# PSX_Radio.net
KiCad netlist of a schematic drawn in EAGLE
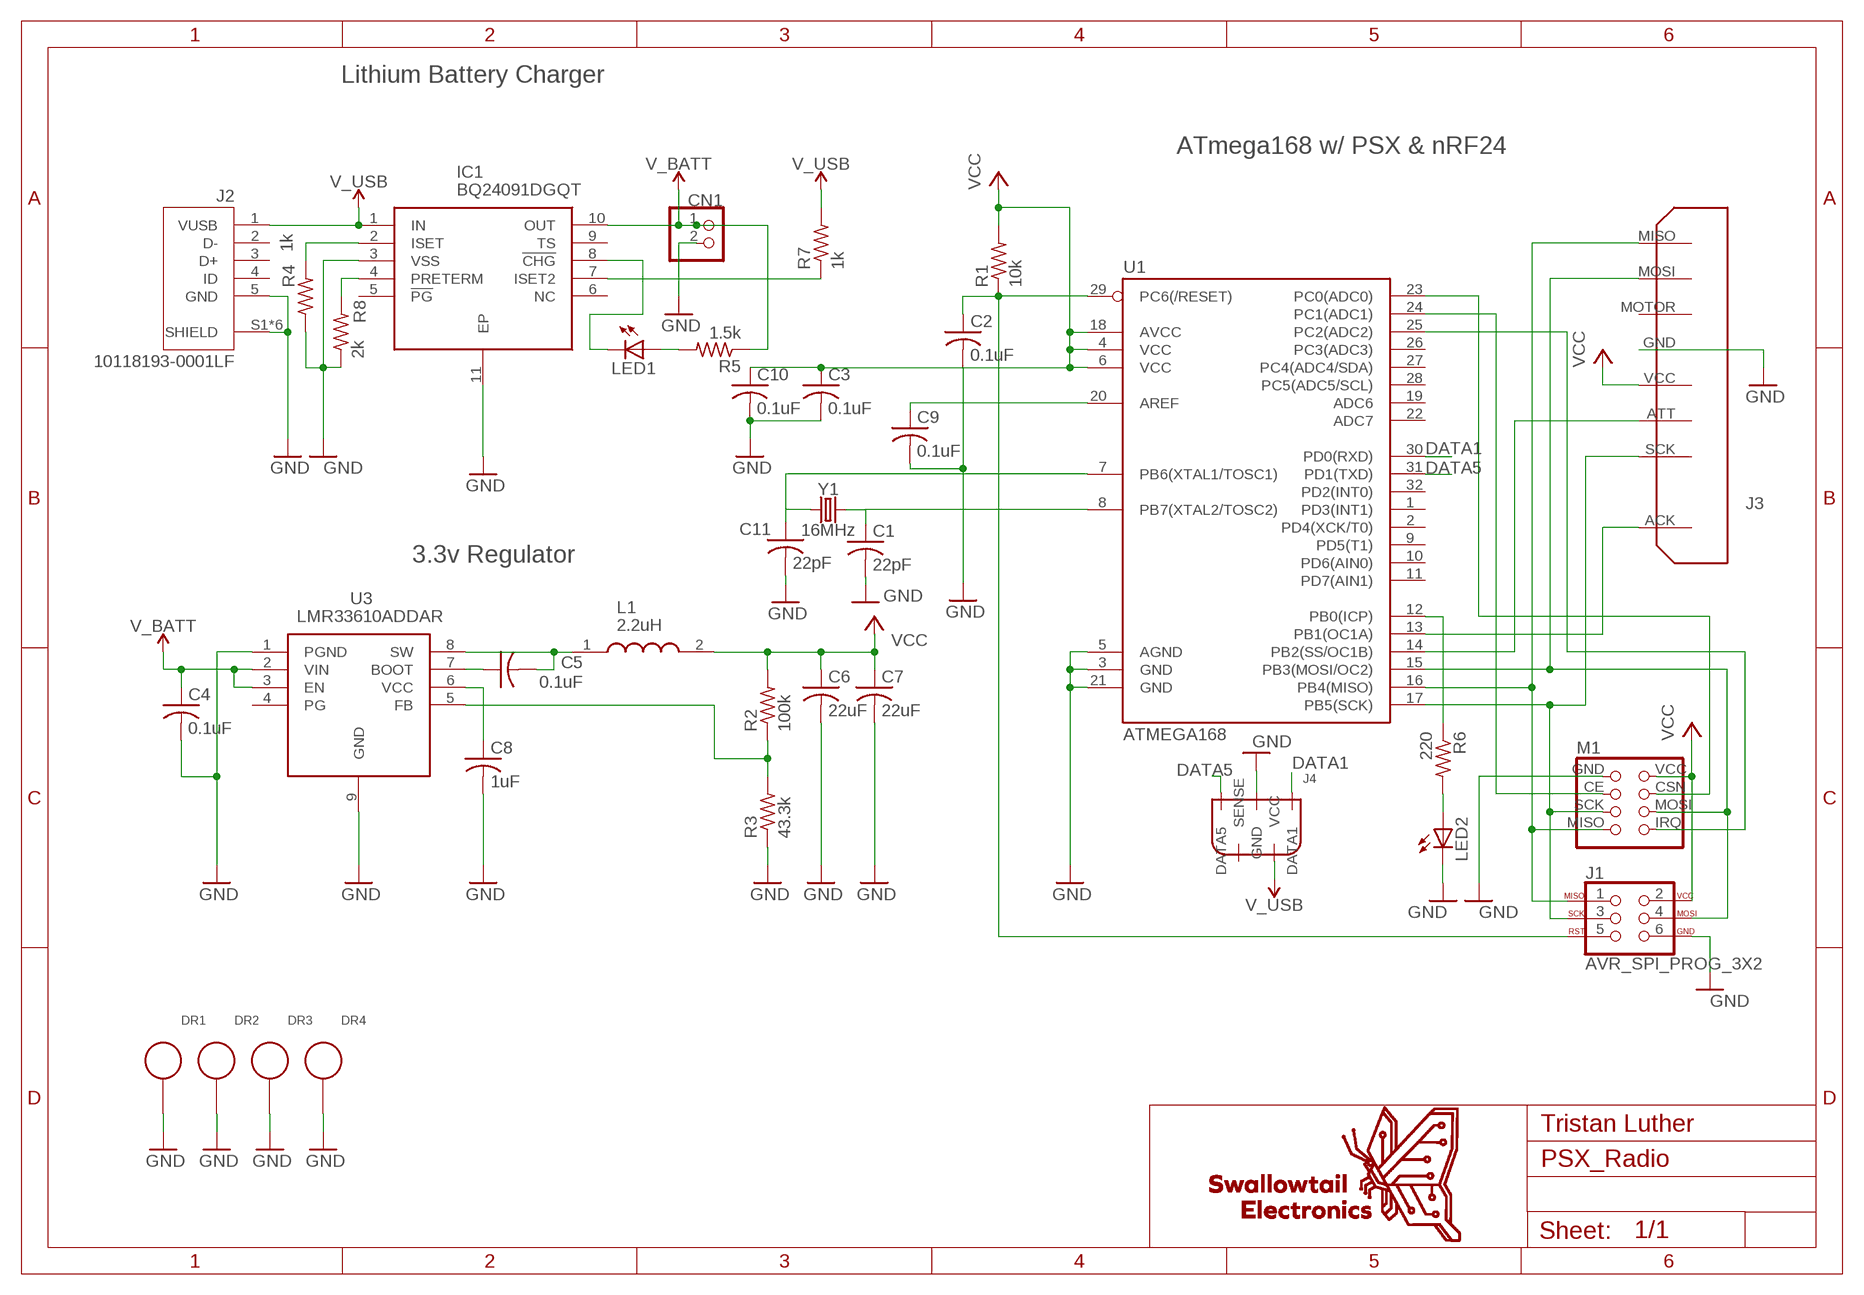
[diagram p0: schematic, sheet 1]

(export (version "E")
  (design (tool "Eeschema 10.0.6"))
  (components
    (comp (ref "C1")
      (value "22pF")
      (footprint "eagle-import:C0805")
      (libsource (lib "eagle-import") (part "C-USC0805"))
    )
    (comp (ref "C2")
      (value "0.1uF")
      (footprint "eagle-import:C0805")
      (libsource (lib "eagle-import") (part "C-USC0805"))
    )
    (comp (ref "C3")
      (value "0.1uF")
      (footprint "eagle-import:C0805")
      (libsource (lib "eagle-import") (part "C-USC0805"))
    )
    (comp (ref "C4")
      (value "0.1uF")
      (footprint "eagle-import:C0805")
      (libsource (lib "eagle-import") (part "C-USC0805"))
    )
    (comp (ref "C5")
      (value "0.1uF")
      (footprint "eagle-import:C0805")
      (libsource (lib "eagle-import") (part "C-USC0805"))
    )
    (comp (ref "C6")
      (value "22uF")
      (footprint "eagle-import:C0805")
      (libsource (lib "eagle-import") (part "C-USC0805"))
    )
    (comp (ref "C7")
      (value "22uF")
      (footprint "eagle-import:C0805")
      (libsource (lib "eagle-import") (part "C-USC0805"))
    )
    (comp (ref "C8")
      (value "1uF")
      (footprint "eagle-import:C0805")
      (libsource (lib "eagle-import") (part "C-USC0805"))
    )
    (comp (ref "C9")
      (value "0.1uF")
      (footprint "eagle-import:C0805")
      (libsource (lib "eagle-import") (part "C-USC0805"))
    )
    (comp (ref "C10")
      (value "0.1uF")
      (footprint "eagle-import:C0805")
      (libsource (lib "eagle-import") (part "C-USC0805"))
    )
    (comp (ref "C11")
      (value "22pF")
      (footprint "eagle-import:C0805")
      (libsource (lib "eagle-import") (part "C-USC0805"))
    )
    (comp (ref "CN1")
      (value "JST_2PIN-SMT-RA")
      (footprint "eagle-import:JST-PH-2-SMT-RA")
      (libsource (lib "eagle-import") (part "JST_2PIN-SMT-RA"))
    )
    (comp (ref "DR1")
      (value "3MM_DRILL_GND")
      (footprint "eagle-import:3MM_DRILL_GND")
      (libsource (lib "eagle-import") (part "3MM_DRILL_GND"))
    )
    (comp (ref "DR2")
      (value "3MM_DRILL_GND")
      (footprint "eagle-import:3MM_DRILL_GND")
      (libsource (lib "eagle-import") (part "3MM_DRILL_GND"))
    )
    (comp (ref "DR3")
      (value "3MM_DRILL_GND")
      (footprint "eagle-import:3MM_DRILL_GND")
      (libsource (lib "eagle-import") (part "3MM_DRILL_GND"))
    )
    (comp (ref "DR4")
      (value "3MM_DRILL_GND")
      (footprint "eagle-import:3MM_DRILL_GND")
      (libsource (lib "eagle-import") (part "3MM_DRILL_GND"))
    )
    (comp (ref "IC1")
      (value "BQ24091DGQT")
      (footprint "eagle-import:SOP50P490X110-11N")
      (fields (field (name "MOUSER_PART_NUMBER") "595-BQ24091DGQT"))
      (libsource (lib "eagle-import") (part "BQ24091DGQT"))
    )
    (comp (ref "J1")
      (value "AVR_SPI_PROG_3X2")
      (footprint "eagle-import:2X3-NS")
      (libsource (lib "eagle-import") (part "AVR_SPI_PROG_3X2"))
    )
    (comp (ref "J2")
      (value "10118193-0001LF")
      (footprint "eagle-import:FCI_10118193-0001LF")
      (fields (field (name "MF") "Amphenol ICC"))
      (libsource (lib "eagle-import") (part "10118193-0001LF"))
    )
    (comp (ref "J3")
      (value "PSX_CONTROLLER")
      (footprint "eagle-import:PSX_VERTICAL")
      (libsource (lib "eagle-import") (part "PSX_CONTROLLER"))
    )
    (comp (ref "J4")
      (value "DREAMCAST_CONTROLLER")
      (footprint "eagle-import:1X06")
      (libsource (lib "eagle-import") (part "DREAMCAST_CONTROLLER"))
    )
    (comp (ref "L1")
      (value "2.2uH")
      (footprint "eagle-import:INDPM5752X150N")
      (fields
        (field (name "ARROW_PART_NUMBER") "SRP5015TA-2R2M")
        (field (name "MOUSER_PART_NUMBER") "652-SRP5015TA-2R2M")
      )
      (libsource (lib "eagle-import") (part "SRP5015TA-2R2M"))
    )
    (comp (ref "LED1")
      (value "LED5MM")
      (footprint "eagle-import:LED5MM")
      (libsource (lib "eagle-import") (part "LED5MM"))
    )
    (comp (ref "LED2")
      (value "LED5MM")
      (footprint "eagle-import:LED5MM")
      (libsource (lib "eagle-import") (part "LED5MM"))
    )
    (comp (ref "M1")
      (value "NRF24L01_MODULE")
      (footprint "eagle-import:2X04")
      (libsource (lib "eagle-import") (part "NRF24L01_MODULE"))
    )
    (comp (ref "R1")
      (value "10k")
      (footprint "eagle-import:R0805")
      (libsource (lib "eagle-import") (part "R-US_R0805"))
    )
    (comp (ref "R2")
      (value "100k")
      (footprint "eagle-import:R0805")
      (libsource (lib "eagle-import") (part "R-US_R0805"))
    )
    (comp (ref "R3")
      (value "43.3k")
      (footprint "eagle-import:R0805")
      (libsource (lib "eagle-import") (part "R-US_R0805"))
    )
    (comp (ref "R4")
      (value "1k")
      (footprint "eagle-import:R0805")
      (libsource (lib "eagle-import") (part "R-US_R0805"))
    )
    (comp (ref "R5")
      (value "1.5k")
      (footprint "eagle-import:R0805")
      (libsource (lib "eagle-import") (part "R-US_R0805"))
    )
    (comp (ref "R6")
      (value "220")
      (footprint "eagle-import:R0805")
      (libsource (lib "eagle-import") (part "R-US_R0805"))
    )
    (comp (ref "R7")
      (value "1k")
      (footprint "eagle-import:R0805")
      (libsource (lib "eagle-import") (part "R-US_R0805"))
    )
    (comp (ref "R8")
      (value "2k")
      (footprint "eagle-import:R0805")
      (libsource (lib "eagle-import") (part "R-US_R0805"))
    )
    (comp (ref "U1")
      (value "ATMEGA168")
      (footprint "eagle-import:TQFP32-08")
      (libsource (lib "eagle-import") (part "ATMEGA168"))
    )
    (comp (ref "U3")
      (value "LMR33610ADDAR")
      (footprint "eagle-import:SOIC127P600X170-9N")
      (fields
        (field (name "ARROW_PART_NUMBER") "LMR33630ADDAR")
        (field (name "MOUSER_PART_NUMBER") "595-LMR33630ADDAR")
      )
      (libsource (lib "eagle-import") (part "LMR33610ADDAR"))
    )
    (comp (ref "Y1")
      (value "16MHz")
      (footprint "eagle-import:CRYSTAL-SMD-5X3.2-4PAD")
      (libsource (lib "eagle-import") (part "CRYSTAL-16MHZSMD-5X3.2"))
    )
  )
  (nets
    (net (code "1") (name "/DATA1") (class "Default")
      (node (ref "J4") (pin "2") (pinfunction "DATA1_2") (pintype "bidirectional"))
      (node (ref "U1") (pin "30") (pinfunction "PD0(RXD)_30") (pintype "bidirectional"))
    )
    (net (code "2") (name "/DATA5") (class "Default")
      (node (ref "J4") (pin "4") (pinfunction "DATA5_4") (pintype "bidirectional"))
      (node (ref "U1") (pin "31") (pinfunction "PD1(TXD)_31") (pintype "bidirectional"))
    )
    (net (code "3") (name "GND") (class "Default")
      (node (ref "C1") (pin "2") (pinfunction "2_2") (pintype "passive"))
      (node (ref "C10") (pin "2") (pinfunction "2_2") (pintype "passive"))
      (node (ref "C11") (pin "2") (pinfunction "2_2") (pintype "passive"))
      (node (ref "C2") (pin "2") (pinfunction "2_2") (pintype "passive"))
      (node (ref "C3") (pin "2") (pinfunction "2_2") (pintype "passive"))
      (node (ref "C4") (pin "2") (pinfunction "2_2") (pintype "passive"))
      (node (ref "C6") (pin "2") (pinfunction "2_2") (pintype "passive"))
      (node (ref "C7") (pin "2") (pinfunction "2_2") (pintype "passive"))
      (node (ref "C8") (pin "2") (pinfunction "2_2") (pintype "passive"))
      (node (ref "C9") (pin "2") (pinfunction "2_2") (pintype "passive"))
      (node (ref "CN1") (pin "2") (pinfunction "1_2") (pintype "passive"))
      (node (ref "DR1") (pin "DR") (pinfunction "D$1_DR") (pintype "bidirectional"))
      (node (ref "DR2") (pin "DR") (pinfunction "D$1_DR") (pintype "bidirectional"))
      (node (ref "DR3") (pin "DR") (pinfunction "D$1_DR") (pintype "bidirectional"))
      (node (ref "DR4") (pin "DR") (pinfunction "D$1_DR") (pintype "bidirectional"))
      (node (ref "IC1") (pin "11") (pinfunction "EP_11") (pintype "bidirectional"))
      (node (ref "IC1") (pin "3") (pinfunction "VSS_3") (pintype "bidirectional"))
      (node (ref "J1") (pin "6") (pinfunction "6_6") (pintype "passive"))
      (node (ref "J2") (pin "5") (pinfunction "GND_5") (pintype "passive"))
      (node (ref "J2") (pin "S1") (pinfunction "SHIELD_S1") (pintype "passive"))
      (node (ref "J2") (pin "S2") (pinfunction "SHIELD_S2") (pintype "passive"))
      (node (ref "J2") (pin "S3") (pinfunction "SHIELD_S3") (pintype "passive"))
      (node (ref "J2") (pin "S4") (pinfunction "SHIELD_S4") (pintype "passive"))
      (node (ref "J2") (pin "S5") (pinfunction "SHIELD_S5") (pintype "passive"))
      (node (ref "J2") (pin "S6") (pinfunction "SHIELD_S6") (pintype "passive"))
      (node (ref "J3") (pin "GND") (pinfunction "GND_GND") (pintype "bidirectional"))
      (node (ref "J4") (pin "5") (pinfunction "GND_5") (pintype "power_in"))
      (node (ref "LED2") (pin "K") (pinfunction "C_K") (pintype "passive"))
      (node (ref "M1") (pin "GND") (pinfunction "GND_GND") (pintype "passive"))
      (node (ref "R3") (pin "1") (pinfunction "1_1") (pintype "passive"))
      (node (ref "R4") (pin "1") (pinfunction "1_1") (pintype "passive"))
      (node (ref "R8") (pin "1") (pinfunction "1_1") (pintype "passive"))
      (node (ref "U1") (pin "21") (pinfunction "GND_21") (pintype "bidirectional"))
      (node (ref "U1") (pin "3") (pinfunction "GND_3") (pintype "bidirectional"))
      (node (ref "U1") (pin "5") (pinfunction "AGND_5") (pintype "bidirectional"))
      (node (ref "U3") (pin "1") (pinfunction "PGND_1") (pintype "bidirectional"))
      (node (ref "U3") (pin "9") (pinfunction "GND_9") (pintype "bidirectional"))
    )
    (net (code "4") (name "Net-(IC1-ISET)") (class "Default")
      (node (ref "IC1") (pin "2") (pinfunction "ISET_2") (pintype "bidirectional"))
      (node (ref "R4") (pin "2") (pinfunction "2_2") (pintype "passive"))
    )
    (net (code "5") (name "Net-(IC1-ISET2)") (class "Default")
      (node (ref "IC1") (pin "7") (pinfunction "ISET2_7") (pintype "bidirectional"))
      (node (ref "R7") (pin "1") (pinfunction "1_1") (pintype "passive"))
    )
    (net (code "6") (name "Net-(IC1-PRETERM)") (class "Default")
      (node (ref "IC1") (pin "4") (pinfunction "PRETERM_4") (pintype "bidirectional"))
      (node (ref "R8") (pin "2") (pinfunction "2_2") (pintype "passive"))
    )
    (net (code "7") (name "Net-(IC1-~{CHG})") (class "Default")
      (node (ref "IC1") (pin "8") (pinfunction "~{CHG}_8") (pintype "bidirectional"))
      (node (ref "LED1") (pin "K") (pinfunction "C_K") (pintype "passive"))
    )
    (net (code "8") (name "Net-(LED1-PadA)") (class "Default")
      (node (ref "LED1") (pin "A") (pinfunction "A_A") (pintype "passive"))
      (node (ref "R5") (pin "2") (pinfunction "2_2") (pintype "passive"))
    )
    (net (code "9") (name "Net-(LED2-PadA)") (class "Default")
      (node (ref "LED2") (pin "A") (pinfunction "A_A") (pintype "passive"))
      (node (ref "R6") (pin "2") (pinfunction "2_2") (pintype "passive"))
    )
    (net (code "10") (name "Net-(U1-AREF)") (class "Default")
      (node (ref "C9") (pin "1") (pinfunction "1_1") (pintype "passive"))
      (node (ref "U1") (pin "20") (pinfunction "AREF_20") (pintype "bidirectional"))
    )
    (net (code "11") (name "Net-(U1-PB0(ICP))") (class "Default")
      (node (ref "R6") (pin "1") (pinfunction "1_1") (pintype "passive"))
      (node (ref "U1") (pin "12") (pinfunction "PB0(ICP)_12") (pintype "bidirectional"))
    )
    (net (code "12") (name "Net-(U1-PB1(OC1A))") (class "Default")
      (node (ref "J3") (pin "ACK") (pinfunction "ACK_ACK") (pintype "bidirectional"))
      (node (ref "U1") (pin "13") (pinfunction "PB1(OC1A)_13") (pintype "bidirectional"))
    )
    (net (code "13") (name "Net-(U1-PB2(SS{slash}OC1B))") (class "Default")
      (node (ref "J3") (pin "ATT") (pinfunction "ATT_ATT") (pintype "bidirectional"))
      (node (ref "U1") (pin "14") (pinfunction "PB2(SS/OC1B)_14") (pintype "bidirectional"))
    )
    (net (code "14") (name "Net-(U1-PB3(MOSI{slash}OC2))") (class "Default")
      (node (ref "J1") (pin "4") (pinfunction "4_4") (pintype "passive"))
      (node (ref "J3") (pin "MOSI") (pinfunction "MOSI_MOSI") (pintype "bidirectional"))
      (node (ref "M1") (pin "MOSI") (pinfunction "MOSI_MOSI") (pintype "passive"))
      (node (ref "U1") (pin "15") (pinfunction "PB3(MOSI/OC2)_15") (pintype "bidirectional"))
    )
    (net (code "15") (name "Net-(U1-PB4(MISO))") (class "Default")
      (node (ref "J1") (pin "1") (pinfunction "1_1") (pintype "passive"))
      (node (ref "J3") (pin "MISO") (pinfunction "MISO_MISO") (pintype "bidirectional"))
      (node (ref "M1") (pin "MISO") (pinfunction "MISO_MISO") (pintype "passive"))
      (node (ref "U1") (pin "16") (pinfunction "PB4(MISO)_16") (pintype "bidirectional"))
    )
    (net (code "16") (name "Net-(U1-PB5(SCK))") (class "Default")
      (node (ref "J1") (pin "3") (pinfunction "3_3") (pintype "passive"))
      (node (ref "J3") (pin "SCK") (pinfunction "SCK_SCK") (pintype "bidirectional"))
      (node (ref "M1") (pin "SCK") (pinfunction "SCK_SCK") (pintype "passive"))
      (node (ref "U1") (pin "17") (pinfunction "PB5(SCK)_17") (pintype "bidirectional"))
    )
    (net (code "17") (name "Net-(U1-PB6(XTAL1{slash}TOSC1))") (class "Default")
      (node (ref "C11") (pin "1") (pinfunction "1_1") (pintype "passive"))
      (node (ref "U1") (pin "7") (pinfunction "PB6(XTAL1/TOSC1)_7") (pintype "bidirectional"))
      (node (ref "Y1") (pin "1") (pinfunction "1_1") (pintype "passive"))
    )
    (net (code "18") (name "Net-(U1-PB7(XTAL2{slash}TOSC2))") (class "Default")
      (node (ref "C1") (pin "1") (pinfunction "1_1") (pintype "passive"))
      (node (ref "U1") (pin "8") (pinfunction "PB7(XTAL2/TOSC2)_8") (pintype "bidirectional"))
      (node (ref "Y1") (pin "3") (pinfunction "2_3") (pintype "passive"))
    )
    (net (code "19") (name "Net-(U1-PC0(ADC0))") (class "Default")
      (node (ref "M1") (pin "CSN") (pinfunction "CSN_CSN") (pintype "passive"))
      (node (ref "U1") (pin "23") (pinfunction "PC0(ADC0)_23") (pintype "bidirectional"))
    )
    (net (code "20") (name "Net-(U1-PC1(ADC1))") (class "Default")
      (node (ref "M1") (pin "CE") (pinfunction "CE_CE") (pintype "passive"))
      (node (ref "U1") (pin "24") (pinfunction "PC1(ADC1)_24") (pintype "bidirectional"))
    )
    (net (code "21") (name "Net-(U1-PC2(ADC2))") (class "Default")
      (node (ref "M1") (pin "IRQ") (pinfunction "IRQ_IRQ") (pintype "passive"))
      (node (ref "U1") (pin "25") (pinfunction "PC2(ADC2)_25") (pintype "bidirectional"))
    )
    (net (code "22") (name "Net-(U1-PC6({slash}RESET))") (class "Default")
      (node (ref "C2") (pin "1") (pinfunction "1_1") (pintype "passive"))
      (node (ref "J1") (pin "5") (pinfunction "5_5") (pintype "passive"))
      (node (ref "R1") (pin "1") (pinfunction "1_1") (pintype "passive"))
      (node (ref "U1") (pin "29") (pinfunction "PC6(/RESET)_29") (pintype "bidirectional"))
    )
    (net (code "23") (name "Net-(U3-BOOT)") (class "Default")
      (node (ref "C5") (pin "1") (pinfunction "1_1") (pintype "passive"))
      (node (ref "U3") (pin "7") (pinfunction "BOOT_7") (pintype "bidirectional"))
    )
    (net (code "24") (name "Net-(U3-FB)") (class "Default")
      (node (ref "R2") (pin "1") (pinfunction "1_1") (pintype "passive"))
      (node (ref "R3") (pin "2") (pinfunction "2_2") (pintype "passive"))
      (node (ref "U3") (pin "5") (pinfunction "FB_5") (pintype "bidirectional"))
    )
    (net (code "25") (name "Net-(U3-SW)") (class "Default")
      (node (ref "C5") (pin "2") (pinfunction "2_2") (pintype "passive"))
      (node (ref "L1") (pin "1") (pinfunction "1_1") (pintype "bidirectional"))
      (node (ref "U3") (pin "8") (pinfunction "SW_8") (pintype "bidirectional"))
    )
    (net (code "26") (name "Net-(U3-VCC)") (class "Default")
      (node (ref "C8") (pin "1") (pinfunction "1_1") (pintype "passive"))
      (node (ref "U3") (pin "6") (pinfunction "VCC_6") (pintype "bidirectional"))
    )
    (net (code "27") (name "VCC") (class "Default")
      (node (ref "C10") (pin "1") (pinfunction "1_1") (pintype "passive"))
      (node (ref "C3") (pin "1") (pinfunction "1_1") (pintype "passive"))
      (node (ref "C6") (pin "1") (pinfunction "1_1") (pintype "passive"))
      (node (ref "C7") (pin "1") (pinfunction "1_1") (pintype "passive"))
      (node (ref "J1") (pin "2") (pinfunction "2_2") (pintype "passive"))
      (node (ref "J3") (pin "VCC") (pinfunction "VCC_VCC") (pintype "bidirectional"))
      (node (ref "L1") (pin "2") (pinfunction "2_2") (pintype "bidirectional"))
      (node (ref "M1") (pin "VCC") (pinfunction "VCC_VCC") (pintype "passive"))
      (node (ref "R1") (pin "2") (pinfunction "2_2") (pintype "passive"))
      (node (ref "R2") (pin "2") (pinfunction "2_2") (pintype "passive"))
      (node (ref "U1") (pin "18") (pinfunction "AVCC_18") (pintype "bidirectional"))
      (node (ref "U1") (pin "4") (pinfunction "VCC_4") (pintype "bidirectional"))
      (node (ref "U1") (pin "6") (pinfunction "VCC_6") (pintype "bidirectional"))
    )
    (net (code "28") (name "V_BATT") (class "Default")
      (node (ref "C4") (pin "1") (pinfunction "1_1") (pintype "passive"))
      (node (ref "CN1") (pin "1") (pinfunction "2_1") (pintype "passive"))
      (node (ref "IC1") (pin "10") (pinfunction "OUT_10") (pintype "bidirectional"))
      (node (ref "R5") (pin "1") (pinfunction "1_1") (pintype "passive"))
      (node (ref "U3") (pin "2") (pinfunction "VIN_2") (pintype "bidirectional"))
      (node (ref "U3") (pin "3") (pinfunction "EN_3") (pintype "bidirectional"))
    )
    (net (code "29") (name "V_USB") (class "Default")
      (node (ref "IC1") (pin "1") (pinfunction "IN_1") (pintype "bidirectional"))
      (node (ref "J2") (pin "1") (pinfunction "VUSB_1") (pintype "passive"))
      (node (ref "J4") (pin "1") (pinfunction "VCC_1") (pintype "power_in"))
      (node (ref "R7") (pin "2") (pinfunction "2_2") (pintype "passive"))
    )
    (net (code "30") (name "unconnected-(IC1-NC-Pad6)") (class "Default")
      (node (ref "IC1") (pin "6") (pinfunction "NC_6") (pintype "no_connect"))
    )
    (net (code "31") (name "unconnected-(IC1-TS-Pad9)") (class "Default")
      (node (ref "IC1") (pin "9") (pinfunction "TS_9") (pintype "bidirectional"))
    )
    (net (code "32") (name "unconnected-(IC1-~{PG}-Pad5)") (class "Default")
      (node (ref "IC1") (pin "5") (pinfunction "~{PG}_5") (pintype "bidirectional"))
    )
    (net (code "33") (name "unconnected-(J2-D+-Pad3)") (class "Default")
      (node (ref "J2") (pin "3") (pinfunction "D+_3") (pintype "passive"))
    )
    (net (code "34") (name "unconnected-(J2-D--Pad2)") (class "Default")
      (node (ref "J2") (pin "2") (pinfunction "D-_2") (pintype "passive"))
    )
    (net (code "35") (name "unconnected-(J2-ID-Pad4)") (class "Default")
      (node (ref "J2") (pin "4") (pinfunction "ID_4") (pintype "passive"))
    )
    (net (code "36") (name "unconnected-(J3-PadMOTOR)") (class "Default")
      (node (ref "J3") (pin "MOTOR") (pinfunction "MOTOR_MOTOR") (pintype "bidirectional"))
    )
    (net (code "37") (name "unconnected-(J4-SENSE-Pad6)") (class "Default")
      (node (ref "J4") (pin "6") (pinfunction "SENSE_6") (pintype "bidirectional"))
    )
    (net (code "38") (name "unconnected-(U1-ADC6-Pad19)") (class "Default")
      (node (ref "U1") (pin "19") (pinfunction "ADC6_19") (pintype "bidirectional"))
    )
    (net (code "39") (name "unconnected-(U1-ADC7-Pad22)") (class "Default")
      (node (ref "U1") (pin "22") (pinfunction "ADC7_22") (pintype "bidirectional"))
    )
    (net (code "40") (name "unconnected-(U1-PC3(ADC3)-Pad26)") (class "Default")
      (node (ref "U1") (pin "26") (pinfunction "PC3(ADC3)_26") (pintype "bidirectional"))
    )
    (net (code "41") (name "unconnected-(U1-PC4(ADC4{slash}SDA)-Pad27)") (class "Default")
      (node (ref "U1") (pin "27") (pinfunction "PC4(ADC4/SDA)_27") (pintype "bidirectional"))
    )
    (net (code "42") (name "unconnected-(U1-PC5(ADC5{slash}SCL)-Pad28)") (class "Default")
      (node (ref "U1") (pin "28") (pinfunction "PC5(ADC5/SCL)_28") (pintype "bidirectional"))
    )
    (net (code "43") (name "unconnected-(U1-PD2(INT0)-Pad32)") (class "Default")
      (node (ref "U1") (pin "32") (pinfunction "PD2(INT0)_32") (pintype "bidirectional"))
    )
    (net (code "44") (name "unconnected-(U1-PD3(INT1)-Pad1)") (class "Default")
      (node (ref "U1") (pin "1") (pinfunction "PD3(INT1)_1") (pintype "bidirectional"))
    )
    (net (code "45") (name "unconnected-(U1-PD4(XCK{slash}T0)-Pad2)") (class "Default")
      (node (ref "U1") (pin "2") (pinfunction "PD4(XCK/T0)_2") (pintype "bidirectional"))
    )
    (net (code "46") (name "unconnected-(U1-PD5(T1)-Pad9)") (class "Default")
      (node (ref "U1") (pin "9") (pinfunction "PD5(T1)_9") (pintype "bidirectional"))
    )
    (net (code "47") (name "unconnected-(U1-PD6(AIN0)-Pad10)") (class "Default")
      (node (ref "U1") (pin "10") (pinfunction "PD6(AIN0)_10") (pintype "bidirectional"))
    )
    (net (code "48") (name "unconnected-(U1-PD7(AIN1)-Pad11)") (class "Default")
      (node (ref "U1") (pin "11") (pinfunction "PD7(AIN1)_11") (pintype "bidirectional"))
    )
    (net (code "49") (name "unconnected-(U3-PG-Pad4)") (class "Default")
      (node (ref "U3") (pin "4") (pinfunction "PG_4") (pintype "bidirectional"))
    )
  )
)
